# IC555.net
KiCad netlist of a schematic drawn in EAGLE
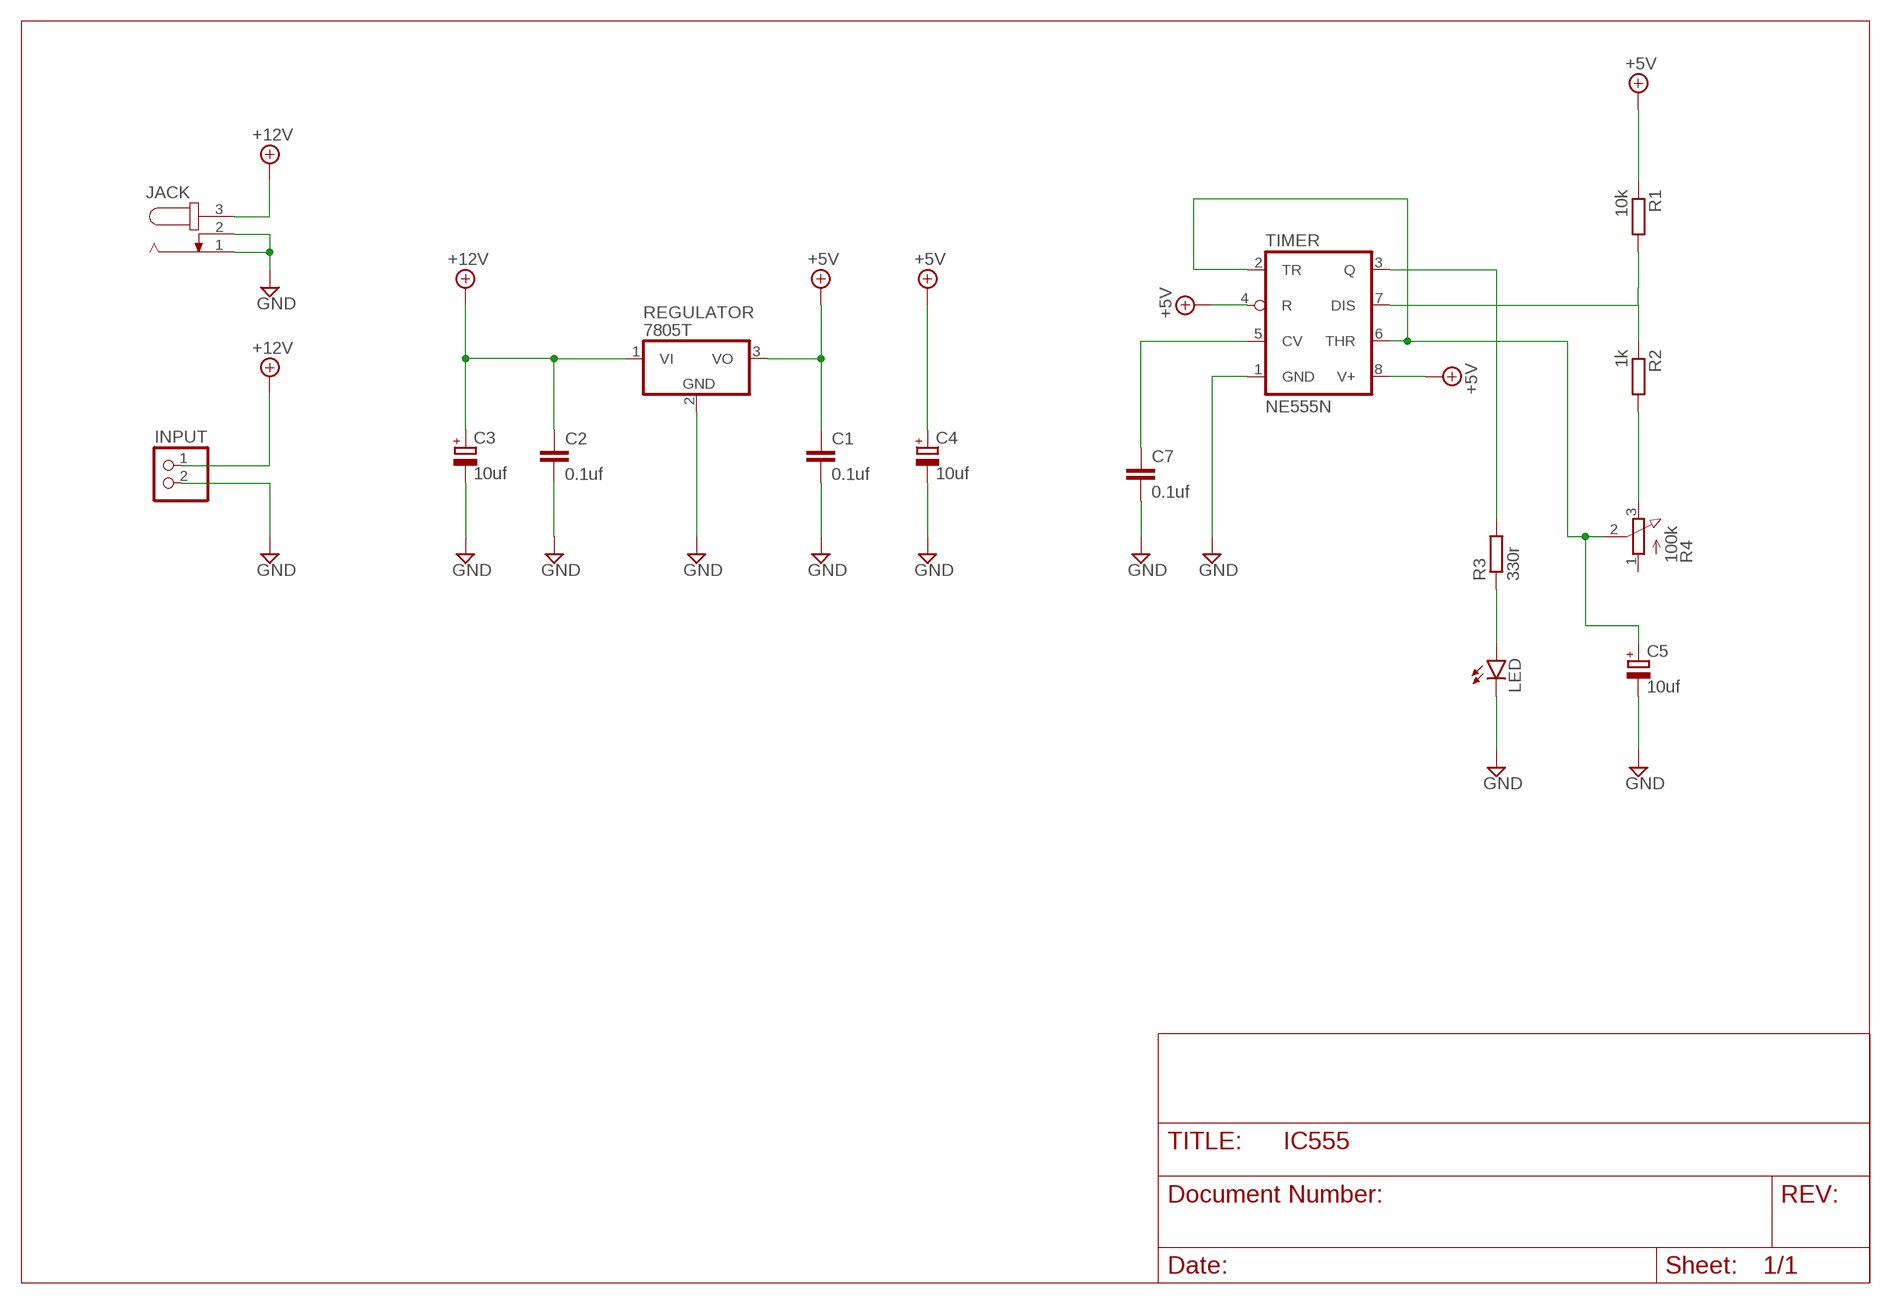
[diagram p0: schematic, sheet 1]

(export (version "E")
  (design (tool "Eeschema 10.0.6"))
  (components
    (comp (ref "C1")
      (value "0.1uf")
      (footprint "eagle-import:C050-030X075")
      (libsource (lib "eagle-import") (part "C-EU050-030X075"))
    )
    (comp (ref "C2")
      (value "0.1uf")
      (footprint "eagle-import:C050-030X075")
      (libsource (lib "eagle-import") (part "C-EU050-030X075"))
    )
    (comp (ref "C3")
      (value "10uf")
      (footprint "eagle-import:E3,5-8")
      (libsource (lib "eagle-import") (part "CPOL-EUE3.5-8"))
    )
    (comp (ref "C4")
      (value "10uf")
      (footprint "eagle-import:E3,5-8")
      (libsource (lib "eagle-import") (part "CPOL-EUE3.5-8"))
    )
    (comp (ref "C5")
      (value "10uf")
      (footprint "eagle-import:E3,5-8")
      (libsource (lib "eagle-import") (part "CPOL-EUE3.5-8"))
    )
    (comp (ref "C7")
      (value "0.1uf")
      (footprint "eagle-import:C050-030X075")
      (libsource (lib "eagle-import") (part "C-EU050-030X075"))
    )
    (comp (ref "INPUT")
      (value "PINHD-1X2")
      (footprint "eagle-import:1X02")
      (libsource (lib "eagle-import") (part "PINHD-1X2"))
    )
    (comp (ref "JACK")
      (value "JACK-PLUG0")
      (footprint "eagle-import:SPC4077")
      (libsource (lib "eagle-import") (part "JACK-PLUG0"))
    )
    (comp (ref "LED")
      (value "LED5MM")
      (footprint "eagle-import:LED5MM")
      (libsource (lib "eagle-import") (part "LED5MM"))
    )
    (comp (ref "R1")
      (value "10k")
      (footprint "eagle-import:0207_10")
      (libsource (lib "eagle-import") (part "R-EU_0207/10"))
    )
    (comp (ref "R2")
      (value "1k")
      (footprint "eagle-import:0207_10")
      (libsource (lib "eagle-import") (part "R-EU_0207/10"))
    )
    (comp (ref "R3")
      (value "330r")
      (footprint "eagle-import:0207_10")
      (libsource (lib "eagle-import") (part "R-EU_0207/10"))
    )
    (comp (ref "R4")
      (value "100k")
      (footprint "eagle-import:3RP_1610N")
      (libsource (lib "eagle-import") (part "3RP/1610N"))
    )
    (comp (ref "REGULATOR")
      (value "7805T")
      (footprint "eagle-import:TO220H")
      (libsource (lib "eagle-import") (part "78T05"))
    )
    (comp (ref "TIMER")
      (value "NE555N")
      (footprint "eagle-import:DIL08")
      (libsource (lib "eagle-import") (part "555NNE"))
    )
  )
  (nets
    (net (code "1") (name "+5V") (class "Default")
      (node (ref "C1") (pin "1") (pinfunction "1_1") (pintype "passive"))
      (node (ref "C4") (pin "+") (pinfunction "+_+") (pintype "passive"))
      (node (ref "R1") (pin "1") (pinfunction "1_1") (pintype "passive"))
      (node (ref "REGULATOR") (pin "3") (pinfunction "VO_3") (pintype "passive"))
      (node (ref "TIMER") (pin "4") (pinfunction "R_4") (pintype "input"))
      (node (ref "TIMER") (pin "8") (pinfunction "V+_8") (pintype "power_in"))
    )
    (net (code "2") (name "+12V") (class "Default")
      (node (ref "C2") (pin "1") (pinfunction "1_1") (pintype "passive"))
      (node (ref "C3") (pin "+") (pinfunction "+_+") (pintype "passive"))
      (node (ref "INPUT") (pin "1") (pinfunction "1_1") (pintype "passive"))
      (node (ref "JACK") (pin "3") (pinfunction "3_3") (pintype "passive"))
      (node (ref "REGULATOR") (pin "1") (pinfunction "VI_1") (pintype "input"))
    )
    (net (code "3") (name "GND") (class "Default")
      (node (ref "C1") (pin "2") (pinfunction "2_2") (pintype "passive"))
      (node (ref "C2") (pin "2") (pinfunction "2_2") (pintype "passive"))
      (node (ref "C3") (pin "-") (pinfunction "-_-") (pintype "passive"))
      (node (ref "C4") (pin "-") (pinfunction "-_-") (pintype "passive"))
      (node (ref "C5") (pin "-") (pinfunction "-_-") (pintype "passive"))
      (node (ref "C7") (pin "2") (pinfunction "2_2") (pintype "passive"))
      (node (ref "INPUT") (pin "2") (pinfunction "2_2") (pintype "passive"))
      (node (ref "JACK") (pin "1") (pinfunction "1_1") (pintype "passive"))
      (node (ref "JACK") (pin "2") (pinfunction "2_2") (pintype "passive"))
      (node (ref "LED") (pin "K") (pinfunction "C_K") (pintype "passive"))
      (node (ref "REGULATOR") (pin "2") (pinfunction "GND_2") (pintype "passive"))
      (node (ref "TIMER") (pin "1") (pinfunction "GND_1") (pintype "power_in"))
    )
    (net (code "4") (name "Net-(LED-PadA)") (class "Default")
      (node (ref "LED") (pin "A") (pinfunction "A_A") (pintype "passive"))
      (node (ref "R3") (pin "1") (pinfunction "1_1") (pintype "passive"))
    )
    (net (code "5") (name "Net-(R4-E)") (class "Default")
      (node (ref "R2") (pin "2") (pinfunction "2_2") (pintype "passive"))
      (node (ref "R4") (pin "3") (pinfunction "E_3") (pintype "passive"))
    )
    (net (code "6") (name "Net-(R4-S)") (class "Default")
      (node (ref "C5") (pin "+") (pinfunction "+_+") (pintype "passive"))
      (node (ref "R4") (pin "2") (pinfunction "S_2") (pintype "passive"))
      (node (ref "TIMER") (pin "2") (pinfunction "TR_2") (pintype "input"))
      (node (ref "TIMER") (pin "6") (pinfunction "THR_6") (pintype "input"))
    )
    (net (code "7") (name "Net-(TIMER-CV)") (class "Default")
      (node (ref "C7") (pin "1") (pinfunction "1_1") (pintype "passive"))
      (node (ref "TIMER") (pin "5") (pinfunction "CV_5") (pintype "input"))
    )
    (net (code "8") (name "Net-(TIMER-DIS)") (class "Default")
      (node (ref "R1") (pin "2") (pinfunction "2_2") (pintype "passive"))
      (node (ref "R2") (pin "1") (pinfunction "1_1") (pintype "passive"))
      (node (ref "TIMER") (pin "7") (pinfunction "DIS_7") (pintype "input"))
    )
    (net (code "9") (name "Net-(TIMER-Q)") (class "Default")
      (node (ref "R3") (pin "2") (pinfunction "2_2") (pintype "passive"))
      (node (ref "TIMER") (pin "3") (pinfunction "Q_3") (pintype "output"))
    )
    (net (code "10") (name "unconnected-(R4-A-Pad1)") (class "Default")
      (node (ref "R4") (pin "1") (pinfunction "A_1") (pintype "passive"))
    )
  )
)
